# 8mixer.net
KiCad netlist of a schematic drawn in EAGLE
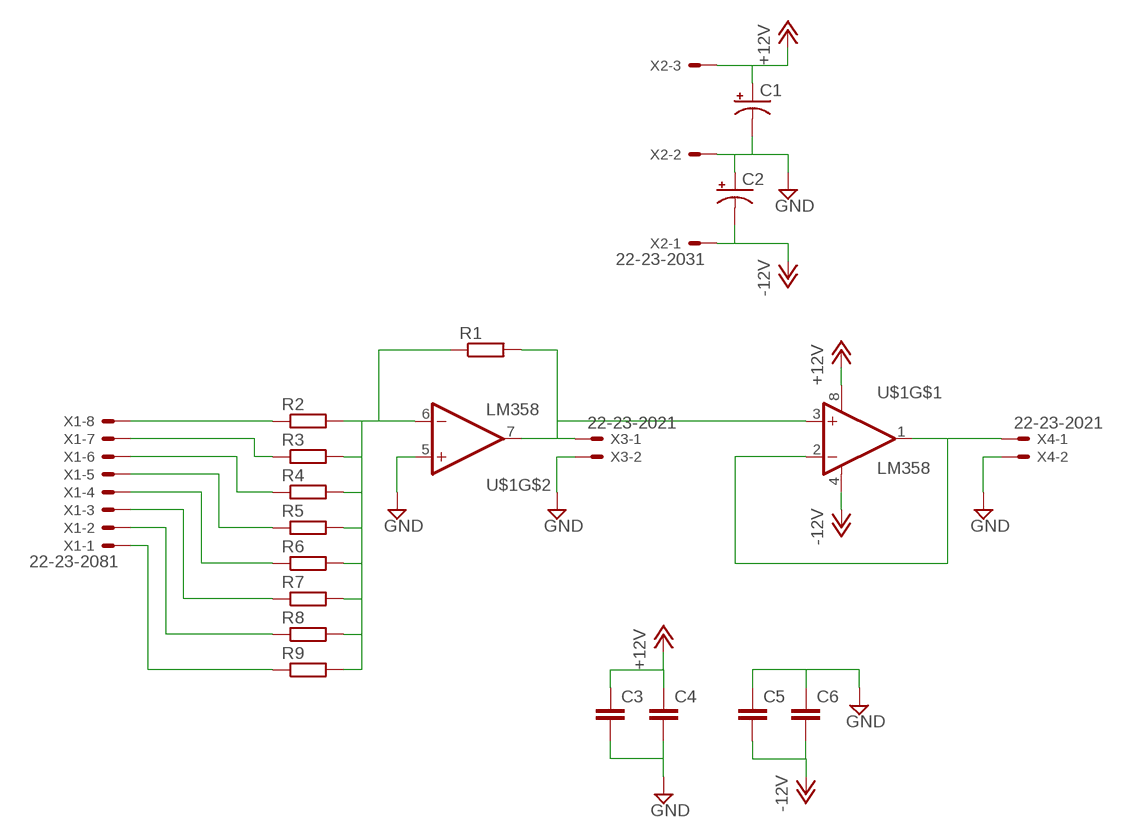
[diagram p0: schematic, sheet 1]

(export (version "E")
  (design (tool "Eeschema 10.0.6"))
  (components
    (comp (ref "C1")
      (value "CPOL-USSMCE")
      (footprint "eagle-import:SMC_E")
      (libsource (lib "eagle-import") (part "CPOL-USSMCE"))
    )
    (comp (ref "C2")
      (value "CPOL-USSMCE")
      (footprint "eagle-import:SMC_E")
      (libsource (lib "eagle-import") (part "CPOL-USSMCE"))
    )
    (comp (ref "C3")
      (value "C-EUC0603K")
      (footprint "eagle-import:C0603K")
      (libsource (lib "eagle-import") (part "C-EUC0603K"))
    )
    (comp (ref "C4")
      (value "C-EUC0603K")
      (footprint "eagle-import:C0603K")
      (libsource (lib "eagle-import") (part "C-EUC0603K"))
    )
    (comp (ref "C5")
      (value "C-EUC0603K")
      (footprint "eagle-import:C0603K")
      (libsource (lib "eagle-import") (part "C-EUC0603K"))
    )
    (comp (ref "C6")
      (value "C-EUC0603K")
      (footprint "eagle-import:C0603K")
      (libsource (lib "eagle-import") (part "C-EUC0603K"))
    )
    (comp (ref "R1")
      (value "R-EU_R0603")
      (footprint "eagle-import:R0603")
      (libsource (lib "eagle-import") (part "R-EU_R0603"))
    )
    (comp (ref "R2")
      (value "R-EU_R0603")
      (footprint "eagle-import:R0603")
      (libsource (lib "eagle-import") (part "R-EU_R0603"))
    )
    (comp (ref "R3")
      (value "R-EU_R0603")
      (footprint "eagle-import:R0603")
      (libsource (lib "eagle-import") (part "R-EU_R0603"))
    )
    (comp (ref "R4")
      (value "R-EU_R0603")
      (footprint "eagle-import:R0603")
      (libsource (lib "eagle-import") (part "R-EU_R0603"))
    )
    (comp (ref "R5")
      (value "R-EU_R0603")
      (footprint "eagle-import:R0603")
      (libsource (lib "eagle-import") (part "R-EU_R0603"))
    )
    (comp (ref "R6")
      (value "R-EU_R0603")
      (footprint "eagle-import:R0603")
      (libsource (lib "eagle-import") (part "R-EU_R0603"))
    )
    (comp (ref "R7")
      (value "R-EU_R0603")
      (footprint "eagle-import:R0603")
      (libsource (lib "eagle-import") (part "R-EU_R0603"))
    )
    (comp (ref "R8")
      (value "R-EU_R0603")
      (footprint "eagle-import:R0603")
      (libsource (lib "eagle-import") (part "R-EU_R0603"))
    )
    (comp (ref "R9")
      (value "R-EU_R0603")
      (footprint "eagle-import:R0603")
      (libsource (lib "eagle-import") (part "R-EU_R0603"))
    )
    (comp (ref "U$1")
      (value "LM358")
      (footprint "eagle-import:SO08")
      (libsource (lib "eagle-import") (part "LM358"))
    )
    (comp (ref "X1")
      (value "22-23-2081")
      (footprint "eagle-import:22-23-2081")
      (fields (field (name "MF") "MOLEX"))
      (libsource (lib "eagle-import") (part "22-23-2081"))
    )
    (comp (ref "X2")
      (value "22-23-2031")
      (footprint "eagle-import:22-23-2031")
      (fields (field (name "MF") "MOLEX"))
      (libsource (lib "eagle-import") (part "22-23-2031"))
    )
    (comp (ref "X3")
      (value "22-23-2021")
      (footprint "eagle-import:22-23-2021")
      (fields (field (name "MF") "MOLEX"))
      (libsource (lib "eagle-import") (part "22-23-2021"))
    )
    (comp (ref "X4")
      (value "22-23-2021")
      (footprint "eagle-import:22-23-2021")
      (fields (field (name "MF") "MOLEX"))
      (libsource (lib "eagle-import") (part "22-23-2021"))
    )
  )
  (nets
    (net (code "1") (name "+12V") (class "Default")
      (node (ref "C1") (pin "+") (pinfunction "+_+") (pintype "passive"))
      (node (ref "C3") (pin "1") (pinfunction "1_1") (pintype "passive"))
      (node (ref "C4") (pin "1") (pinfunction "1_1") (pintype "passive"))
      (node (ref "U$1") (pin "8") (pinfunction "V+_8") (pintype "power_in"))
      (node (ref "X2") (pin "3") (pinfunction "S_3") (pintype "passive"))
    )
    (net (code "2") (name "-12V") (class "Default")
      (node (ref "C2") (pin "-") (pinfunction "-_-") (pintype "passive"))
      (node (ref "C5") (pin "2") (pinfunction "2_2") (pintype "passive"))
      (node (ref "C6") (pin "2") (pinfunction "2_2") (pintype "passive"))
      (node (ref "U$1") (pin "4") (pinfunction "V-_4") (pintype "power_in"))
      (node (ref "X2") (pin "1") (pinfunction "S_1") (pintype "passive"))
    )
    (net (code "3") (name "GND") (class "Default")
      (node (ref "C1") (pin "-") (pinfunction "-_-") (pintype "passive"))
      (node (ref "C2") (pin "+") (pinfunction "+_+") (pintype "passive"))
      (node (ref "C3") (pin "2") (pinfunction "2_2") (pintype "passive"))
      (node (ref "C4") (pin "2") (pinfunction "2_2") (pintype "passive"))
      (node (ref "C5") (pin "1") (pinfunction "1_1") (pintype "passive"))
      (node (ref "C6") (pin "1") (pinfunction "1_1") (pintype "passive"))
      (node (ref "U$1") (pin "5") (pinfunction "+IN_5") (pintype "input"))
      (node (ref "X2") (pin "2") (pinfunction "S_2") (pintype "passive"))
      (node (ref "X3") (pin "2") (pinfunction "S_2") (pintype "passive"))
      (node (ref "X4") (pin "2") (pinfunction "S_2") (pintype "passive"))
    )
    (net (code "4") (name "Net-(U$1A-+IN)") (class "Default")
      (node (ref "R1") (pin "2") (pinfunction "2_2") (pintype "passive"))
      (node (ref "U$1") (pin "3") (pinfunction "+IN_3") (pintype "input"))
      (node (ref "U$1") (pin "7") (pinfunction "OUT_7") (pintype "output"))
      (node (ref "X3") (pin "1") (pinfunction "S_1") (pintype "passive"))
    )
    (net (code "5") (name "Net-(U$1A--IN)") (class "Default")
      (node (ref "U$1") (pin "1") (pinfunction "OUT_1") (pintype "output"))
      (node (ref "U$1") (pin "2") (pinfunction "-IN_2") (pintype "input"))
      (node (ref "X4") (pin "1") (pinfunction "S_1") (pintype "passive"))
    )
    (net (code "6") (name "Net-(U$1B--IN)") (class "Default")
      (node (ref "R1") (pin "1") (pinfunction "1_1") (pintype "passive"))
      (node (ref "R2") (pin "2") (pinfunction "2_2") (pintype "passive"))
      (node (ref "R3") (pin "2") (pinfunction "2_2") (pintype "passive"))
      (node (ref "R4") (pin "2") (pinfunction "2_2") (pintype "passive"))
      (node (ref "R5") (pin "2") (pinfunction "2_2") (pintype "passive"))
      (node (ref "R6") (pin "2") (pinfunction "2_2") (pintype "passive"))
      (node (ref "R7") (pin "2") (pinfunction "2_2") (pintype "passive"))
      (node (ref "R8") (pin "2") (pinfunction "2_2") (pintype "passive"))
      (node (ref "R9") (pin "2") (pinfunction "2_2") (pintype "passive"))
      (node (ref "U$1") (pin "6") (pinfunction "-IN_6") (pintype "input"))
    )
    (net (code "7") (name "Net-(X1A-S)") (class "Default")
      (node (ref "R9") (pin "1") (pinfunction "1_1") (pintype "passive"))
      (node (ref "X1") (pin "1") (pinfunction "S_1") (pintype "passive"))
    )
    (net (code "8") (name "Net-(X1B-S)") (class "Default")
      (node (ref "R8") (pin "1") (pinfunction "1_1") (pintype "passive"))
      (node (ref "X1") (pin "2") (pinfunction "S_2") (pintype "passive"))
    )
    (net (code "9") (name "Net-(X1C-S)") (class "Default")
      (node (ref "R7") (pin "1") (pinfunction "1_1") (pintype "passive"))
      (node (ref "X1") (pin "3") (pinfunction "S_3") (pintype "passive"))
    )
    (net (code "10") (name "Net-(X1D-S)") (class "Default")
      (node (ref "R6") (pin "1") (pinfunction "1_1") (pintype "passive"))
      (node (ref "X1") (pin "4") (pinfunction "S_4") (pintype "passive"))
    )
    (net (code "11") (name "Net-(X1E-S)") (class "Default")
      (node (ref "R5") (pin "1") (pinfunction "1_1") (pintype "passive"))
      (node (ref "X1") (pin "5") (pinfunction "S_5") (pintype "passive"))
    )
    (net (code "12") (name "Net-(X1F-S)") (class "Default")
      (node (ref "R4") (pin "1") (pinfunction "1_1") (pintype "passive"))
      (node (ref "X1") (pin "6") (pinfunction "S_6") (pintype "passive"))
    )
    (net (code "13") (name "Net-(X1G-S)") (class "Default")
      (node (ref "R3") (pin "1") (pinfunction "1_1") (pintype "passive"))
      (node (ref "X1") (pin "7") (pinfunction "S_7") (pintype "passive"))
    )
    (net (code "14") (name "Net-(X1H-S)") (class "Default")
      (node (ref "R2") (pin "1") (pinfunction "1_1") (pintype "passive"))
      (node (ref "X1") (pin "8") (pinfunction "S_8") (pintype "passive"))
    )
  )
)
